# SAMD21.net
KiCad netlist of a schematic drawn in EAGLE
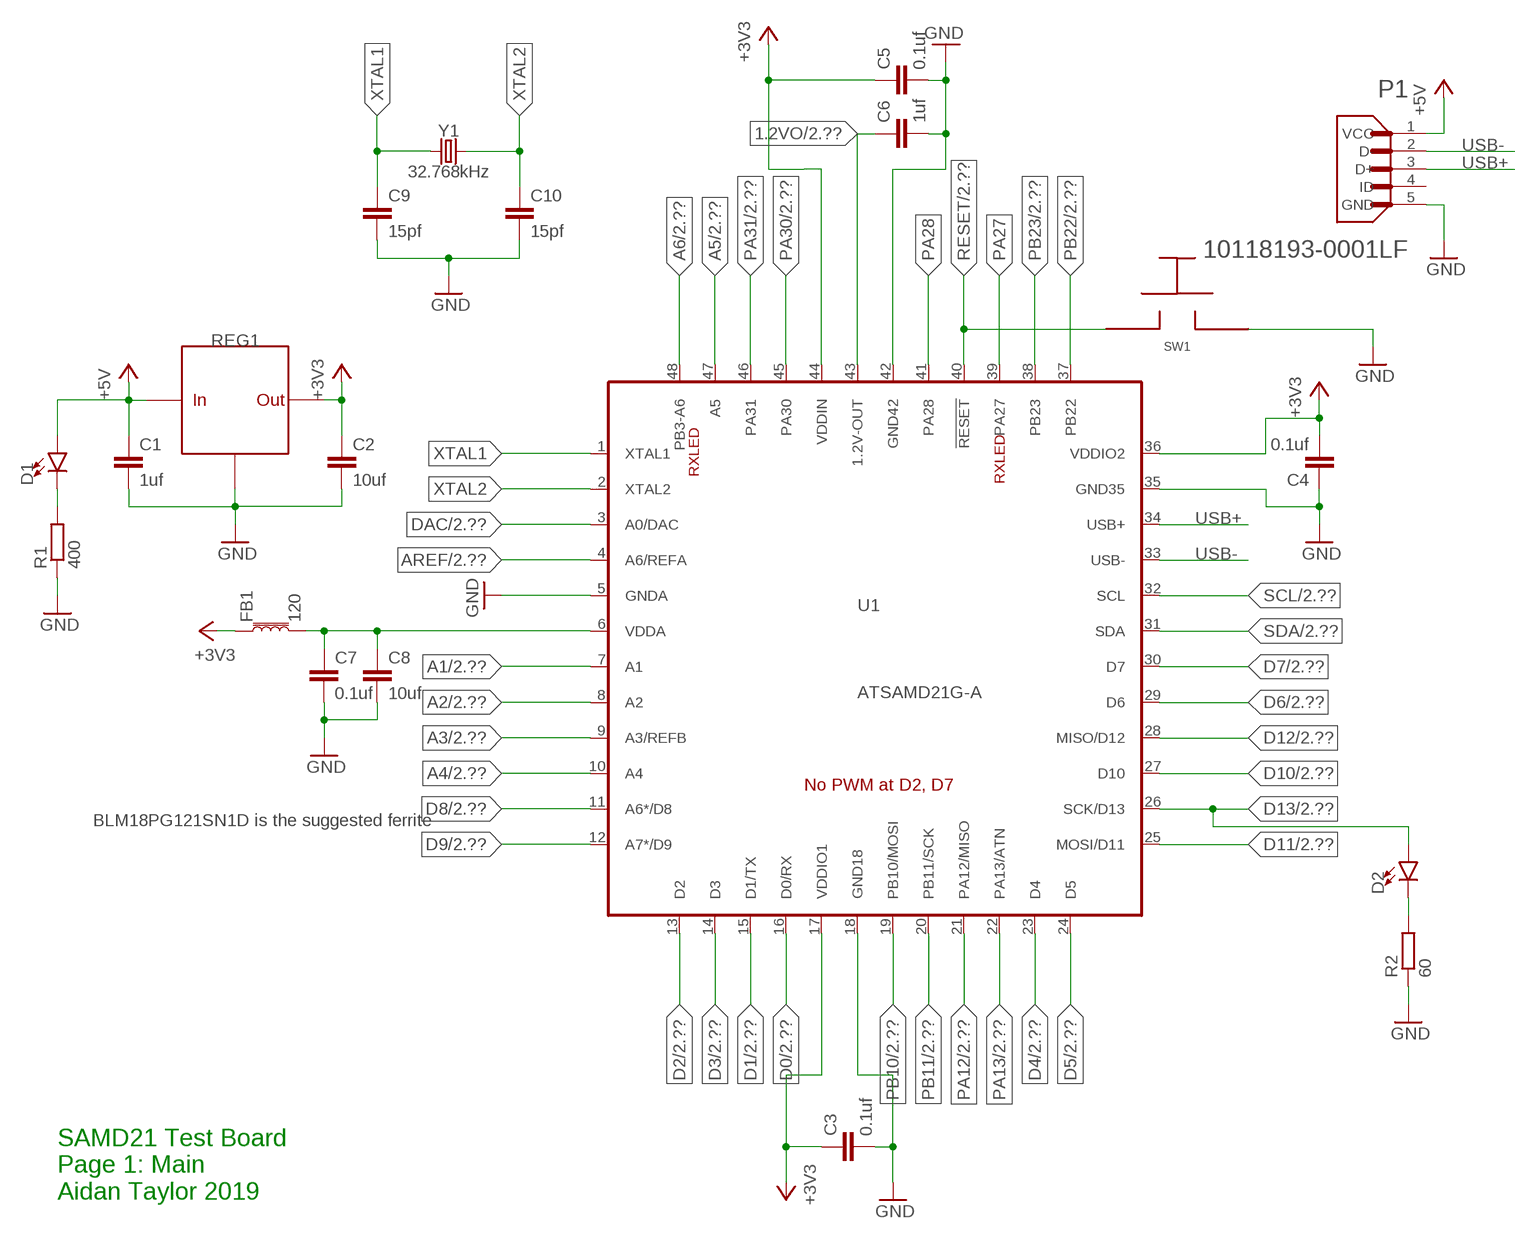
[diagram p0: schematic, sheet 1]
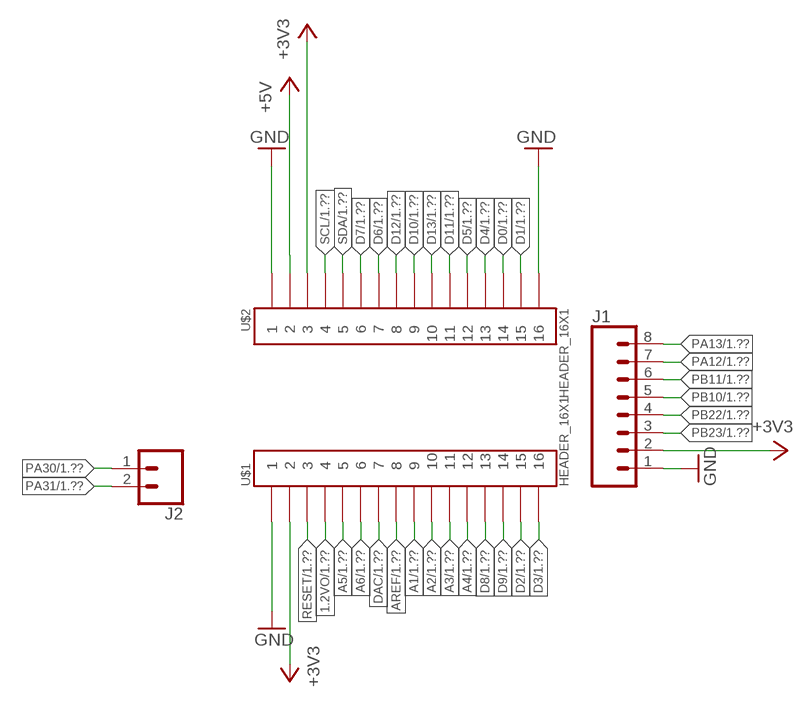
[diagram p1: schematic, sheet 2]

(export (version "E")
  (design (tool "Eeschema 10.0.6"))
  (components
    (comp (ref "C1")
      (value "1uf")
      (footprint "eagle-import:C0805")
      (libsource (lib "eagle-import") (part "C-EUC0805"))
    )
    (comp (ref "C2")
      (value "10uf")
      (footprint "eagle-import:C0805")
      (libsource (lib "eagle-import") (part "C-EUC0805"))
    )
    (comp (ref "C3")
      (value "0.1uf")
      (footprint "eagle-import:C0603")
      (libsource (lib "eagle-import") (part "C-EUC0603"))
    )
    (comp (ref "C4")
      (value "0.1uf")
      (footprint "eagle-import:C0603")
      (libsource (lib "eagle-import") (part "C-EUC0603"))
    )
    (comp (ref "C5")
      (value "0.1uf")
      (footprint "eagle-import:C0603")
      (libsource (lib "eagle-import") (part "C-EUC0603"))
    )
    (comp (ref "C6")
      (value "1uf")
      (footprint "eagle-import:C0805")
      (libsource (lib "eagle-import") (part "C-EUC0805"))
    )
    (comp (ref "C7")
      (value "0.1uf")
      (footprint "eagle-import:C0603")
      (libsource (lib "eagle-import") (part "C-EUC0603"))
    )
    (comp (ref "C8")
      (value "10uf")
      (footprint "eagle-import:C0805")
      (libsource (lib "eagle-import") (part "C-EUC0805"))
    )
    (comp (ref "C9")
      (value "15pf")
      (footprint "eagle-import:C0603")
      (libsource (lib "eagle-import") (part "C-EUC0603"))
    )
    (comp (ref "C10")
      (value "15pf")
      (footprint "eagle-import:C0603")
      (libsource (lib "eagle-import") (part "C-EUC0603"))
    )
    (comp (ref "D1")
      (value "LED0603")
      (footprint "eagle-import:LED-0603")
      (libsource (lib "eagle-import") (part "LED0603"))
    )
    (comp (ref "D2")
      (value "LED0603")
      (footprint "eagle-import:LED-0603")
      (libsource (lib "eagle-import") (part "LED0603"))
    )
    (comp (ref "FB1")
      (value "120")
      (footprint "eagle-import:0603")
      (libsource (lib "eagle-import") (part "FERRITE_BEAD-0603"))
    )
    (comp (ref "P1")
      (value "10118193-0001LF")
      (footprint "eagle-import:FCI_10118193-0001LF")
      (fields (field (name "MF") "Amphenol FCI"))
      (libsource (lib "eagle-import") (part "10118193-0001LF"))
    )
    (comp (ref "R1")
      (value "400")
      (footprint "eagle-import:R0603")
      (libsource (lib "eagle-import") (part "R-EU_R0603"))
    )
    (comp (ref "R2")
      (value "60")
      (footprint "eagle-import:R0603")
      (libsource (lib "eagle-import") (part "R-EU_R0603"))
    )
    (comp (ref "REG1")
      (value "TLV1117LV33DCYT")
      (footprint "eagle-import:SOT223")
      (libsource (lib "eagle-import") (part "TLV1117LV33DCYT"))
    )
    (comp (ref "SW1")
      (value "KXT3_LOWPROFILE_SMDSWITCH")
      (footprint "eagle-import:KXT3_SMD_SWITCH")
      (libsource (lib "eagle-import") (part "KXT3_LOWPROFILE_SMDSWITCH"))
    )
    (comp (ref "U1")
      (value "ATSAMD21G-A")
      (footprint "eagle-import:TQFP-48")
      (libsource (lib "eagle-import") (part "ATSAMD21G-A"))
    )
    (comp (ref "Y1")
      (value "32.768kHz")
      (footprint "eagle-import:CRYSTAL-SMD-3.2X1.5MM")
      (libsource (lib "eagle-import") (part "CRYSTAL-32.768KHZSMD-3.2X1.5"))
    )
    (comp (ref "J1")
      (value "CONN_08\"")
      (footprint "eagle-import:1X08")
      (libsource (lib "eagle-import") (part "CONN_08{dblquote}"))
    )
    (comp (ref "J2")
      (value "CONN_02")
      (footprint "eagle-import:1X02")
      (libsource (lib "eagle-import") (part "CONN_02"))
    )
    (comp (ref "U$1")
      (value "HEADER_16X1")
      (footprint "eagle-import:HDRV16W64P254_1X16_4064X254X900B_NO_SILK")
      (libsource (lib "eagle-import") (part "HEADER_16X1"))
    )
    (comp (ref "U$2")
      (value "HEADER_16X1")
      (footprint "eagle-import:HDRV16W64P254_1X16_4064X254X900B_NO_SILK")
      (libsource (lib "eagle-import") (part "HEADER_16X1"))
    )
  )
  (nets
    (net (code "1") (name "+3V3") (class "Default")
      (node (ref "C2") (pin "1") (pinfunction "1_1") (pintype "passive"))
      (node (ref "C3") (pin "1") (pinfunction "1_1") (pintype "passive"))
      (node (ref "C4") (pin "2") (pinfunction "2_2") (pintype "passive"))
      (node (ref "C5") (pin "1") (pinfunction "1_1") (pintype "passive"))
      (node (ref "FB1") (pin "1") (pinfunction "1_1") (pintype "passive"))
      (node (ref "J1") (pin "2") (pinfunction "2_2") (pintype "passive"))
      (node (ref "REG1") (pin "2") (pinfunction "VOUT_2") (pintype "power_in"))
      (node (ref "REG1") (pin "4") (pinfunction "VOUT_4") (pintype "power_in"))
      (node (ref "U$1") (pin "P$2") (pinfunction "2_P$2") (pintype "bidirectional"))
      (node (ref "U$2") (pin "P$3") (pinfunction "3_P$3") (pintype "bidirectional"))
      (node (ref "U1") (pin "17") (pinfunction "VDDIO1_17") (pintype "bidirectional"))
      (node (ref "U1") (pin "36") (pinfunction "VDDIO2_36") (pintype "bidirectional"))
      (node (ref "U1") (pin "44") (pinfunction "VDDIN_44") (pintype "bidirectional"))
    )
    (net (code "2") (name "+5V") (class "Default")
      (node (ref "C1") (pin "1") (pinfunction "1_1") (pintype "passive"))
      (node (ref "D1") (pin "A") (pinfunction "A_A") (pintype "passive"))
      (node (ref "P1") (pin "1") (pinfunction "VCC_1") (pintype "power_in"))
      (node (ref "REG1") (pin "3") (pinfunction "VIN_3") (pintype "power_in"))
      (node (ref "U$2") (pin "P$2") (pinfunction "2_P$2") (pintype "bidirectional"))
    )
    (net (code "3") (name "1.2VO") (class "Default")
      (node (ref "C6") (pin "1") (pinfunction "1_1") (pintype "passive"))
      (node (ref "U$1") (pin "P$4") (pinfunction "4_P$4") (pintype "bidirectional"))
      (node (ref "U1") (pin "43") (pinfunction "1.2V-OUT_43") (pintype "bidirectional"))
    )
    (net (code "4") (name "A1") (class "Default")
      (node (ref "U$1") (pin "P$9") (pinfunction "9_P$9") (pintype "bidirectional"))
      (node (ref "U1") (pin "7") (pinfunction "A1_7") (pintype "bidirectional"))
    )
    (net (code "5") (name "A2") (class "Default")
      (node (ref "U$1") (pin "P$10") (pinfunction "10_P$10") (pintype "bidirectional"))
      (node (ref "U1") (pin "8") (pinfunction "A2_8") (pintype "bidirectional"))
    )
    (net (code "6") (name "A3") (class "Default")
      (node (ref "U$1") (pin "P$11") (pinfunction "11_P$11") (pintype "bidirectional"))
      (node (ref "U1") (pin "9") (pinfunction "A3/REFB_9") (pintype "bidirectional"))
    )
    (net (code "7") (name "A4") (class "Default")
      (node (ref "U$1") (pin "P$12") (pinfunction "12_P$12") (pintype "bidirectional"))
      (node (ref "U1") (pin "10") (pinfunction "A4_10") (pintype "bidirectional"))
    )
    (net (code "8") (name "A5") (class "Default")
      (node (ref "U$1") (pin "P$5") (pinfunction "5_P$5") (pintype "bidirectional"))
      (node (ref "U1") (pin "47") (pinfunction "A5_47") (pintype "bidirectional"))
    )
    (net (code "9") (name "A6") (class "Default")
      (node (ref "U$1") (pin "P$6") (pinfunction "6_P$6") (pintype "bidirectional"))
      (node (ref "U1") (pin "48") (pinfunction "PB3-A6_48") (pintype "bidirectional"))
    )
    (net (code "10") (name "AREF") (class "Default")
      (node (ref "U$1") (pin "P$8") (pinfunction "8_P$8") (pintype "bidirectional"))
      (node (ref "U1") (pin "4") (pinfunction "A6/REFA_4") (pintype "bidirectional"))
    )
    (net (code "11") (name "D0") (class "Default")
      (node (ref "U$2") (pin "P$14") (pinfunction "14_P$14") (pintype "bidirectional"))
      (node (ref "U1") (pin "16") (pinfunction "D0/RX_16") (pintype "bidirectional"))
    )
    (net (code "12") (name "D1") (class "Default")
      (node (ref "U$2") (pin "P$15") (pinfunction "15_P$15") (pintype "bidirectional"))
      (node (ref "U1") (pin "15") (pinfunction "D1/TX_15") (pintype "bidirectional"))
    )
    (net (code "13") (name "D2") (class "Default")
      (node (ref "U$1") (pin "P$15") (pinfunction "15_P$15") (pintype "bidirectional"))
      (node (ref "U1") (pin "13") (pinfunction "D2_13") (pintype "bidirectional"))
    )
    (net (code "14") (name "D3") (class "Default")
      (node (ref "U$1") (pin "P$16") (pinfunction "16_P$16") (pintype "bidirectional"))
      (node (ref "U1") (pin "14") (pinfunction "D3_14") (pintype "bidirectional"))
    )
    (net (code "15") (name "D4") (class "Default")
      (node (ref "U$2") (pin "P$13") (pinfunction "13_P$13") (pintype "bidirectional"))
      (node (ref "U1") (pin "23") (pinfunction "D4_23") (pintype "bidirectional"))
    )
    (net (code "16") (name "D5") (class "Default")
      (node (ref "U$2") (pin "P$12") (pinfunction "12_P$12") (pintype "bidirectional"))
      (node (ref "U1") (pin "24") (pinfunction "D5_24") (pintype "bidirectional"))
    )
    (net (code "17") (name "D6") (class "Default")
      (node (ref "U$2") (pin "P$7") (pinfunction "7_P$7") (pintype "bidirectional"))
      (node (ref "U1") (pin "29") (pinfunction "D6_29") (pintype "bidirectional"))
    )
    (net (code "18") (name "D7") (class "Default")
      (node (ref "U$2") (pin "P$6") (pinfunction "6_P$6") (pintype "bidirectional"))
      (node (ref "U1") (pin "30") (pinfunction "D7_30") (pintype "bidirectional"))
    )
    (net (code "19") (name "D8") (class "Default")
      (node (ref "U$1") (pin "P$13") (pinfunction "13_P$13") (pintype "bidirectional"))
      (node (ref "U1") (pin "11") (pinfunction "A6*/D8_11") (pintype "bidirectional"))
    )
    (net (code "20") (name "D9") (class "Default")
      (node (ref "U$1") (pin "P$14") (pinfunction "14_P$14") (pintype "bidirectional"))
      (node (ref "U1") (pin "12") (pinfunction "A7*/D9_12") (pintype "bidirectional"))
    )
    (net (code "21") (name "D10") (class "Default")
      (node (ref "U$2") (pin "P$9") (pinfunction "9_P$9") (pintype "bidirectional"))
      (node (ref "U1") (pin "27") (pinfunction "D10_27") (pintype "bidirectional"))
    )
    (net (code "22") (name "D11") (class "Default")
      (node (ref "U$2") (pin "P$11") (pinfunction "11_P$11") (pintype "bidirectional"))
      (node (ref "U1") (pin "25") (pinfunction "MOSI/D11_25") (pintype "bidirectional"))
    )
    (net (code "23") (name "D12") (class "Default")
      (node (ref "U$2") (pin "P$8") (pinfunction "8_P$8") (pintype "bidirectional"))
      (node (ref "U1") (pin "28") (pinfunction "MISO/D12_28") (pintype "bidirectional"))
    )
    (net (code "24") (name "D13") (class "Default")
      (node (ref "D2") (pin "A") (pinfunction "A_A") (pintype "passive"))
      (node (ref "U$2") (pin "P$10") (pinfunction "10_P$10") (pintype "bidirectional"))
      (node (ref "U1") (pin "26") (pinfunction "SCK/D13_26") (pintype "bidirectional"))
    )
    (net (code "25") (name "DAC") (class "Default")
      (node (ref "U$1") (pin "P$7") (pinfunction "7_P$7") (pintype "bidirectional"))
      (node (ref "U1") (pin "3") (pinfunction "A0/DAC_3") (pintype "bidirectional"))
    )
    (net (code "26") (name "GND") (class "Default")
      (node (ref "C1") (pin "2") (pinfunction "2_2") (pintype "passive"))
      (node (ref "C10") (pin "2") (pinfunction "2_2") (pintype "passive"))
      (node (ref "C2") (pin "2") (pinfunction "2_2") (pintype "passive"))
      (node (ref "C3") (pin "2") (pinfunction "2_2") (pintype "passive"))
      (node (ref "C4") (pin "1") (pinfunction "1_1") (pintype "passive"))
      (node (ref "C5") (pin "2") (pinfunction "2_2") (pintype "passive"))
      (node (ref "C6") (pin "2") (pinfunction "2_2") (pintype "passive"))
      (node (ref "C7") (pin "2") (pinfunction "2_2") (pintype "passive"))
      (node (ref "C8") (pin "2") (pinfunction "2_2") (pintype "passive"))
      (node (ref "C9") (pin "2") (pinfunction "2_2") (pintype "passive"))
      (node (ref "J1") (pin "1") (pinfunction "1_1") (pintype "passive"))
      (node (ref "P1") (pin "5") (pinfunction "GND_5") (pintype "passive"))
      (node (ref "R1") (pin "1") (pinfunction "1_1") (pintype "passive"))
      (node (ref "R2") (pin "1") (pinfunction "1_1") (pintype "passive"))
      (node (ref "REG1") (pin "1") (pinfunction "GND_1") (pintype "power_in"))
      (node (ref "SW1") (pin "P$2") (pinfunction "P$2_P$2") (pintype "bidirectional"))
      (node (ref "U$1") (pin "P$1") (pinfunction "1_P$1") (pintype "bidirectional"))
      (node (ref "U$2") (pin "P$1") (pinfunction "1_P$1") (pintype "bidirectional"))
      (node (ref "U$2") (pin "P$16") (pinfunction "16_P$16") (pintype "bidirectional"))
      (node (ref "U1") (pin "18") (pinfunction "GND18_18") (pintype "bidirectional"))
      (node (ref "U1") (pin "35") (pinfunction "GND35_35") (pintype "bidirectional"))
      (node (ref "U1") (pin "42") (pinfunction "GND42_42") (pintype "bidirectional"))
      (node (ref "U1") (pin "5") (pinfunction "GNDA_5") (pintype "bidirectional"))
    )
    (net (code "27") (name "Net-(D1-PadC)") (class "Default")
      (node (ref "D1") (pin "C") (pinfunction "C_C") (pintype "passive"))
      (node (ref "R1") (pin "2") (pinfunction "2_2") (pintype "passive"))
    )
    (net (code "28") (name "Net-(D2-PadC)") (class "Default")
      (node (ref "D2") (pin "C") (pinfunction "C_C") (pintype "passive"))
      (node (ref "R2") (pin "2") (pinfunction "2_2") (pintype "passive"))
    )
    (net (code "29") (name "Net-(U1-VDDA)") (class "Default")
      (node (ref "C7") (pin "1") (pinfunction "1_1") (pintype "passive"))
      (node (ref "C8") (pin "1") (pinfunction "1_1") (pintype "passive"))
      (node (ref "FB1") (pin "2") (pinfunction "2_2") (pintype "passive"))
      (node (ref "U1") (pin "6") (pinfunction "VDDA_6") (pintype "bidirectional"))
    )
    (net (code "30") (name "PA12") (class "Default")
      (node (ref "J1") (pin "7") (pinfunction "7_7") (pintype "passive"))
      (node (ref "U1") (pin "21") (pinfunction "PA12/MISO_21") (pintype "bidirectional"))
    )
    (net (code "31") (name "PA13") (class "Default")
      (node (ref "J1") (pin "8") (pinfunction "8_8") (pintype "passive"))
      (node (ref "U1") (pin "22") (pinfunction "PA13/ATN_22") (pintype "bidirectional"))
    )
    (net (code "32") (name "PA27") (class "Default")
      (node (ref "U1") (pin "39") (pinfunction "PA27_39") (pintype "bidirectional"))
    )
    (net (code "33") (name "PA28") (class "Default")
      (node (ref "U1") (pin "41") (pinfunction "PA28_41") (pintype "bidirectional"))
    )
    (net (code "34") (name "PA30") (class "Default")
      (node (ref "J2") (pin "1") (pinfunction "1_1") (pintype "passive"))
      (node (ref "U1") (pin "45") (pinfunction "PA30_45") (pintype "bidirectional"))
    )
    (net (code "35") (name "PA31") (class "Default")
      (node (ref "J2") (pin "2") (pinfunction "2_2") (pintype "passive"))
      (node (ref "U1") (pin "46") (pinfunction "PA31_46") (pintype "bidirectional"))
    )
    (net (code "36") (name "PB10") (class "Default")
      (node (ref "J1") (pin "5") (pinfunction "5_5") (pintype "passive"))
      (node (ref "U1") (pin "19") (pinfunction "PB10/MOSI_19") (pintype "bidirectional"))
    )
    (net (code "37") (name "PB11") (class "Default")
      (node (ref "J1") (pin "6") (pinfunction "6_6") (pintype "passive"))
      (node (ref "U1") (pin "20") (pinfunction "PB11/SCK_20") (pintype "bidirectional"))
    )
    (net (code "38") (name "PB22") (class "Default")
      (node (ref "J1") (pin "4") (pinfunction "4_4") (pintype "passive"))
      (node (ref "U1") (pin "37") (pinfunction "PB22_37") (pintype "bidirectional"))
    )
    (net (code "39") (name "PB23") (class "Default")
      (node (ref "J1") (pin "3") (pinfunction "3_3") (pintype "passive"))
      (node (ref "U1") (pin "38") (pinfunction "PB23_38") (pintype "bidirectional"))
    )
    (net (code "40") (name "RESET") (class "Default")
      (node (ref "SW1") (pin "P$1") (pinfunction "P$1_P$1") (pintype "bidirectional"))
      (node (ref "U$1") (pin "P$3") (pinfunction "3_P$3") (pintype "bidirectional"))
      (node (ref "U1") (pin "40") (pinfunction "~{RESET}_40") (pintype "bidirectional"))
    )
    (net (code "41") (name "SCL") (class "Default")
      (node (ref "U$2") (pin "P$4") (pinfunction "4_P$4") (pintype "bidirectional"))
      (node (ref "U1") (pin "32") (pinfunction "SCL_32") (pintype "bidirectional"))
    )
    (net (code "42") (name "SDA") (class "Default")
      (node (ref "U$2") (pin "P$5") (pinfunction "5_P$5") (pintype "bidirectional"))
      (node (ref "U1") (pin "31") (pinfunction "SDA_31") (pintype "bidirectional"))
    )
    (net (code "43") (name "USB+") (class "Default")
      (node (ref "P1") (pin "3") (pinfunction "D+_3") (pintype "bidirectional"))
      (node (ref "U1") (pin "34") (pinfunction "USB+_34") (pintype "bidirectional"))
    )
    (net (code "44") (name "USB-") (class "Default")
      (node (ref "P1") (pin "2") (pinfunction "D-_2") (pintype "bidirectional"))
      (node (ref "U1") (pin "33") (pinfunction "USB-_33") (pintype "bidirectional"))
    )
    (net (code "45") (name "XTAL1") (class "Default")
      (node (ref "C9") (pin "1") (pinfunction "1_1") (pintype "passive"))
      (node (ref "U1") (pin "1") (pinfunction "XTAL1_1") (pintype "bidirectional"))
      (node (ref "Y1") (pin "P$1") (pinfunction "1_P$1") (pintype "passive"))
    )
    (net (code "46") (name "XTAL2") (class "Default")
      (node (ref "C10") (pin "1") (pinfunction "1_1") (pintype "passive"))
      (node (ref "U1") (pin "2") (pinfunction "XTAL2_2") (pintype "bidirectional"))
      (node (ref "Y1") (pin "P$2") (pinfunction "2_P$2") (pintype "passive"))
    )
    (net (code "47") (name "unconnected-(P1-ID-Pad4)") (class "Default")
      (node (ref "P1") (pin "4") (pinfunction "ID_4") (pintype "bidirectional"))
    )
  )
)
